# SSB_Transceiver_LC_Lowpass_Filter.net
KiCad netlist of a schematic drawn in EAGLE
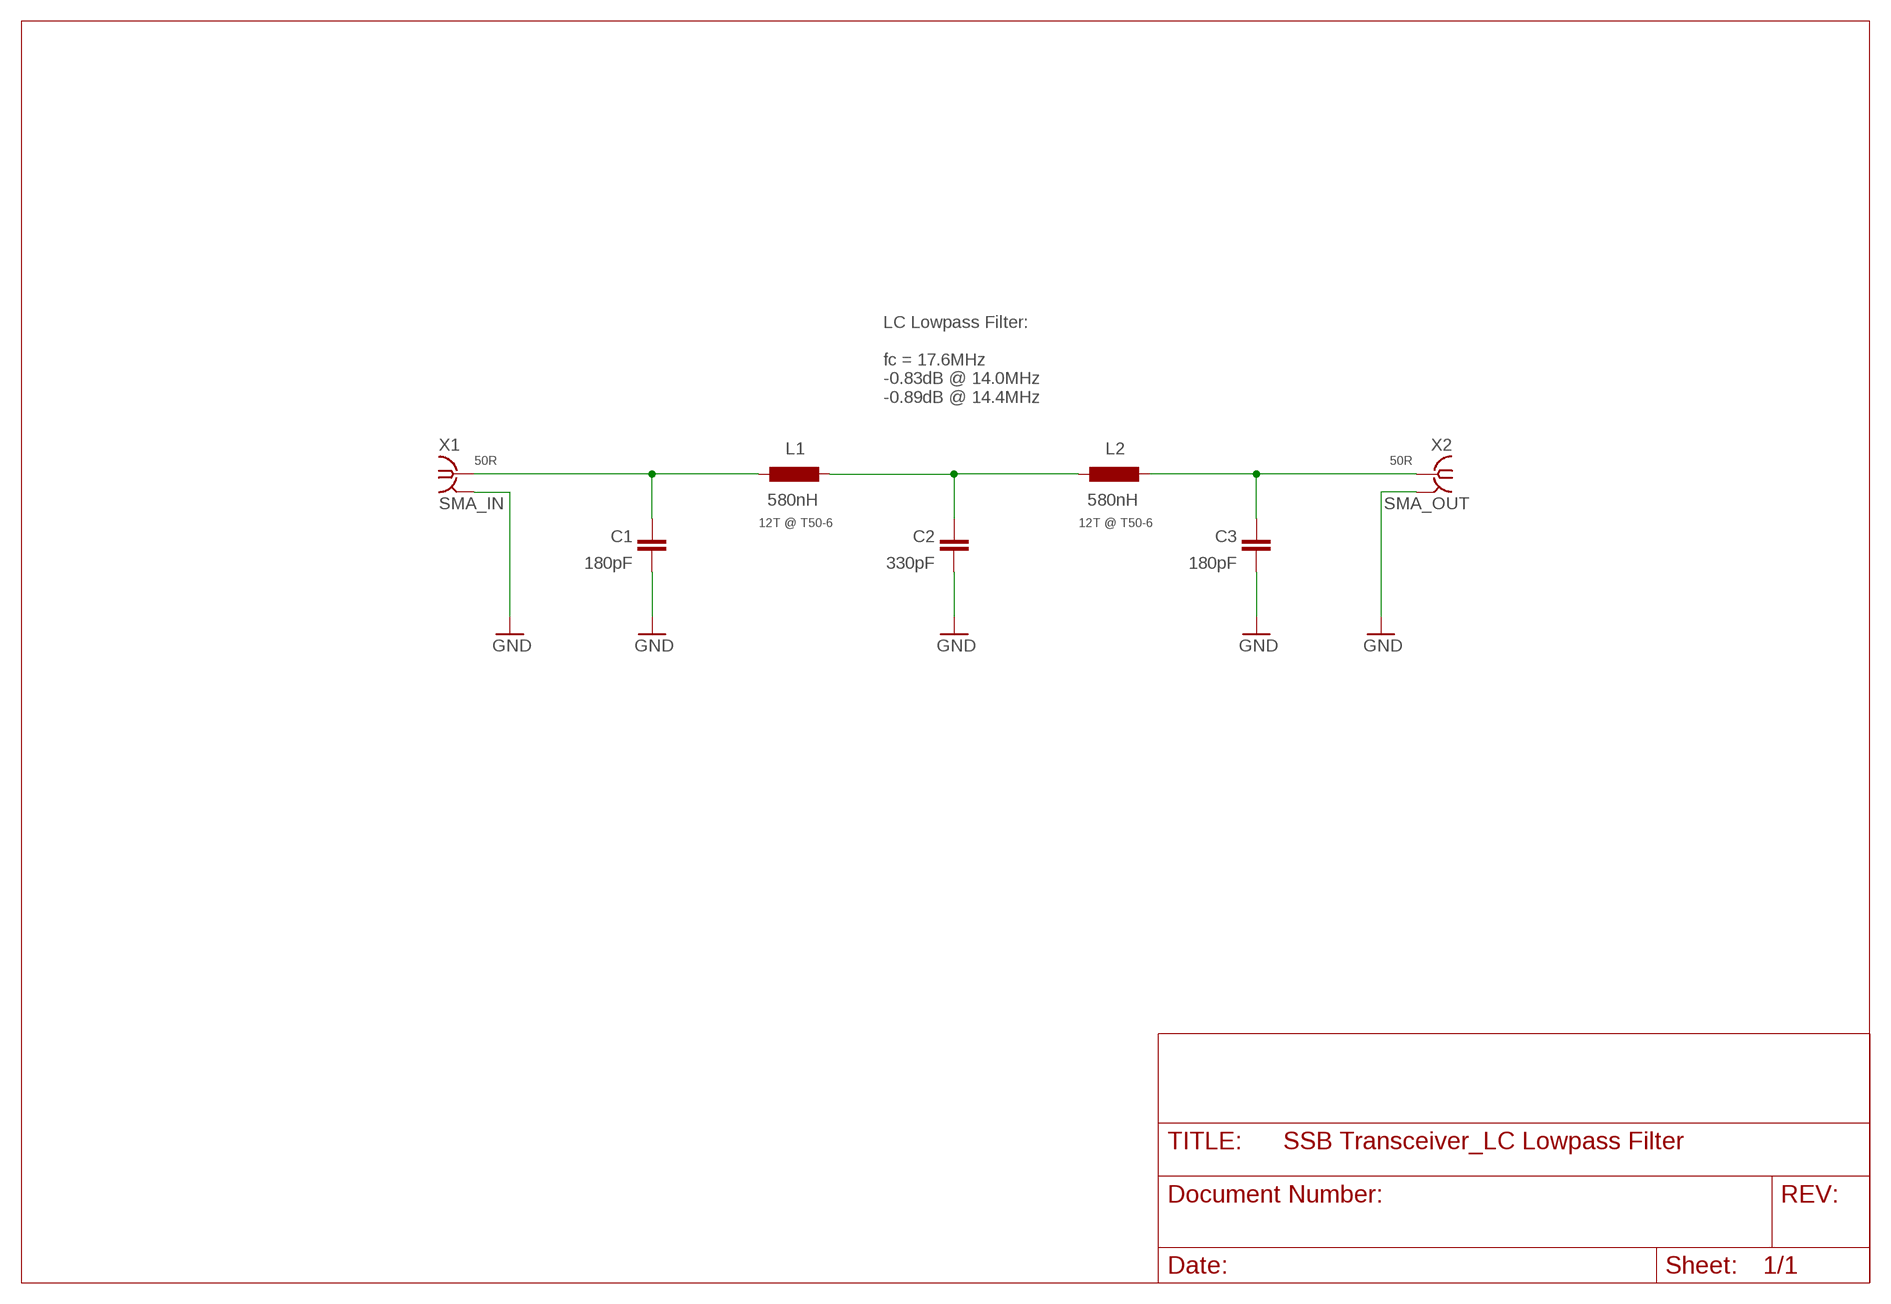
[diagram p0: schematic, sheet 1]

(export (version "E")
  (design (tool "Eeschema 10.0.6"))
  (components
    (comp (ref "C1")
      (value "180pF")
      (footprint "eagle-import:C0805")
      (libsource (lib "eagle-import") (part "C-EUC0805"))
    )
    (comp (ref "C2")
      (value "330pF")
      (footprint "eagle-import:C0805")
      (libsource (lib "eagle-import") (part "C-EUC0805"))
    )
    (comp (ref "C3")
      (value "180pF")
      (footprint "eagle-import:C0805")
      (libsource (lib "eagle-import") (part "C-EUC0805"))
    )
    (comp (ref "L1")
      (value "580nH")
      (footprint "eagle-import:T50-6SMD")
      (libsource (lib "eagle-import") (part "T50-6"))
    )
    (comp (ref "L2")
      (value "580nH")
      (footprint "eagle-import:T50-6SMD")
      (libsource (lib "eagle-import") (part "T50-6"))
    )
    (comp (ref "X1")
      (value "SMA_IN")
      (footprint "eagle-import:J502-ND-142-0711-821_826")
      (fields (field (name "MF") "JOHNSON COMPONENTS") (field (name "MPN") "142-0711-821"))
      (libsource (lib "eagle-import") (part "SMA-142-0711-821/826"))
    )
    (comp (ref "X2")
      (value "SMA_OUT")
      (footprint "eagle-import:J502-ND-142-0711-821_826")
      (fields (field (name "MF") "JOHNSON COMPONENTS") (field (name "MPN") "142-0711-821"))
      (libsource (lib "eagle-import") (part "SMA-142-0711-821/826"))
    )
  )
  (nets
    (net (code "1") (name "GND") (class "Default")
      (node (ref "C1") (pin "1") (pinfunction "1_1") (pintype "passive"))
      (node (ref "C2") (pin "1") (pinfunction "1_1") (pintype "passive"))
      (node (ref "C3") (pin "1") (pinfunction "1_1") (pintype "passive"))
      (node (ref "X1") (pin "G@1") (pinfunction "2_G@1") (pintype "passive"))
      (node (ref "X1") (pin "G@2") (pinfunction "2_G@2") (pintype "passive"))
      (node (ref "X1") (pin "G@3") (pinfunction "2_G@3") (pintype "passive"))
      (node (ref "X1") (pin "G@4") (pinfunction "2_G@4") (pintype "passive"))
      (node (ref "X2") (pin "G@1") (pinfunction "2_G@1") (pintype "passive"))
      (node (ref "X2") (pin "G@2") (pinfunction "2_G@2") (pintype "passive"))
      (node (ref "X2") (pin "G@3") (pinfunction "2_G@3") (pintype "passive"))
      (node (ref "X2") (pin "G@4") (pinfunction "2_G@4") (pintype "passive"))
    )
    (net (code "2") (name "Net-(L1-1)") (class "Default")
      (node (ref "C1") (pin "2") (pinfunction "2_2") (pintype "passive"))
      (node (ref "L1") (pin "P$1") (pinfunction "1_P$1") (pintype "passive"))
      (node (ref "X1") (pin "1") (pinfunction "1_1") (pintype "passive"))
    )
    (net (code "3") (name "Net-(L1-2)") (class "Default")
      (node (ref "C2") (pin "2") (pinfunction "2_2") (pintype "passive"))
      (node (ref "L1") (pin "P$2") (pinfunction "2_P$2") (pintype "passive"))
      (node (ref "L2") (pin "P$1") (pinfunction "1_P$1") (pintype "passive"))
    )
    (net (code "4") (name "Net-(L2-2)") (class "Default")
      (node (ref "C3") (pin "2") (pinfunction "2_2") (pintype "passive"))
      (node (ref "L2") (pin "P$2") (pinfunction "2_P$2") (pintype "passive"))
      (node (ref "X2") (pin "1") (pinfunction "1_1") (pintype "passive"))
    )
  )
)
